# driver_led_v12.net
KiCad netlist of a schematic drawn in EAGLE
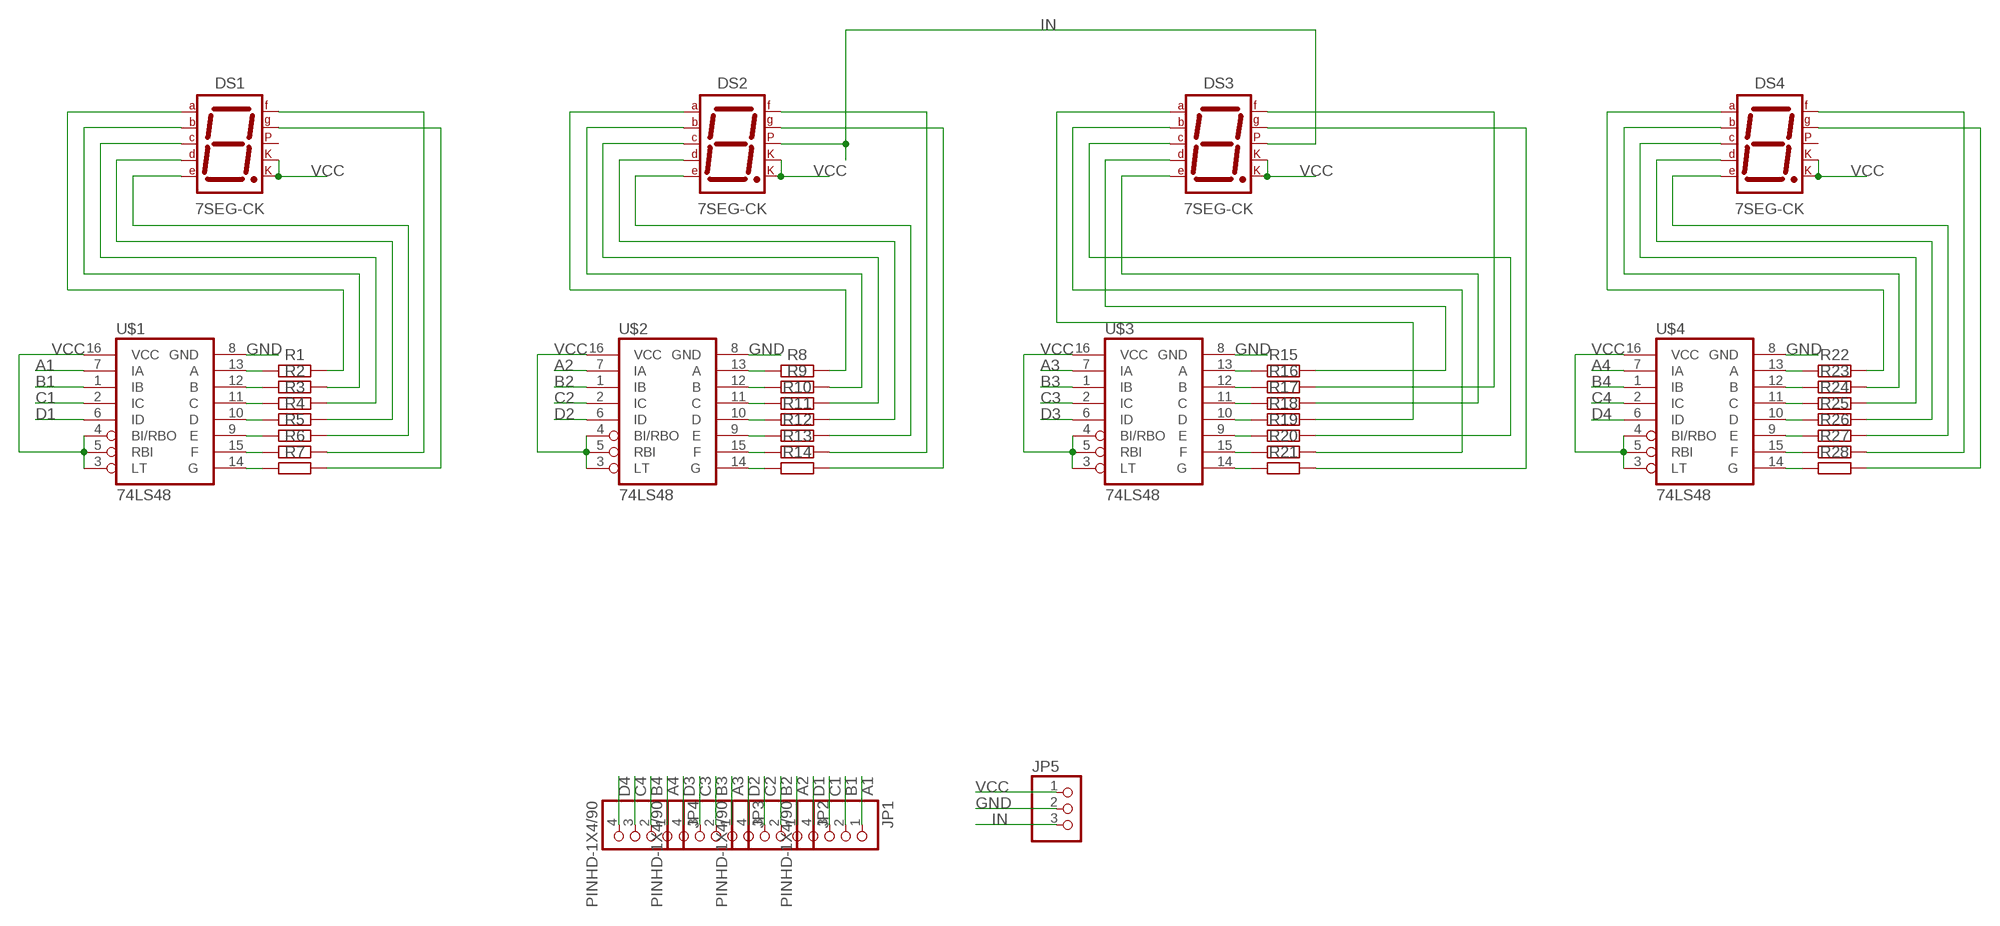
[diagram p0: schematic, sheet 1]

(export (version "E")
  (design (tool "Eeschema 10.0.6"))
  (components
    (comp (ref "DS1")
      (value "7SEG-CK")
      (footprint "eagle-import:7SEG-13")
      (libsource (lib "eagle-import") (part "7SEG-CK"))
    )
    (comp (ref "DS2")
      (value "7SEG-CK")
      (footprint "eagle-import:7SEG-13")
      (libsource (lib "eagle-import") (part "7SEG-CK"))
    )
    (comp (ref "DS3")
      (value "7SEG-CK")
      (footprint "eagle-import:7SEG-13")
      (libsource (lib "eagle-import") (part "7SEG-CK"))
    )
    (comp (ref "DS4")
      (value "7SEG-CK")
      (footprint "eagle-import:7SEG-13")
      (libsource (lib "eagle-import") (part "7SEG-CK"))
    )
    (comp (ref "JP1")
      (value "PINHD-1X4/90")
      (footprint "eagle-import:1X04_90")
      (libsource (lib "eagle-import") (part "PINHD-1X4/90"))
    )
    (comp (ref "JP2")
      (value "PINHD-1X4/90")
      (footprint "eagle-import:1X04_90")
      (libsource (lib "eagle-import") (part "PINHD-1X4/90"))
    )
    (comp (ref "JP3")
      (value "PINHD-1X4/90")
      (footprint "eagle-import:1X04_90")
      (libsource (lib "eagle-import") (part "PINHD-1X4/90"))
    )
    (comp (ref "JP4")
      (value "PINHD-1X4/90")
      (footprint "eagle-import:1X04_90")
      (libsource (lib "eagle-import") (part "PINHD-1X4/90"))
    )
    (comp (ref "JP5")
      (value "PINHD-1X3CB")
      (footprint "eagle-import:1X03-CLEANBIG")
      (libsource (lib "eagle-import") (part "PINHD-1X3CB"))
    )
    (comp (ref "R1")
      (value "R_AXIAL-7.2MM-PITCH")
      (footprint "eagle-import:RESAD724W46L381D178B")
      (libsource (lib "eagle-import") (part "RAXIAL-7.2MM-PITCH_"))
    )
    (comp (ref "R2")
      (value "R_AXIAL-7.2MM-PITCH")
      (footprint "eagle-import:RESAD724W46L381D178B")
      (libsource (lib "eagle-import") (part "RAXIAL-7.2MM-PITCH_"))
    )
    (comp (ref "R3")
      (value "R_AXIAL-7.2MM-PITCH")
      (footprint "eagle-import:RESAD724W46L381D178B")
      (libsource (lib "eagle-import") (part "RAXIAL-7.2MM-PITCH_"))
    )
    (comp (ref "R4")
      (value "R_AXIAL-7.2MM-PITCH")
      (footprint "eagle-import:RESAD724W46L381D178B")
      (libsource (lib "eagle-import") (part "RAXIAL-7.2MM-PITCH_"))
    )
    (comp (ref "R5")
      (value "R_AXIAL-7.2MM-PITCH")
      (footprint "eagle-import:RESAD724W46L381D178B")
      (libsource (lib "eagle-import") (part "RAXIAL-7.2MM-PITCH_"))
    )
    (comp (ref "R6")
      (value "R_AXIAL-7.2MM-PITCH")
      (footprint "eagle-import:RESAD724W46L381D178B")
      (libsource (lib "eagle-import") (part "RAXIAL-7.2MM-PITCH_"))
    )
    (comp (ref "R7")
      (value "R_AXIAL-7.2MM-PITCH")
      (footprint "eagle-import:RESAD724W46L381D178B")
      (libsource (lib "eagle-import") (part "RAXIAL-7.2MM-PITCH_"))
    )
    (comp (ref "R8")
      (value "R_AXIAL-7.2MM-PITCH")
      (footprint "eagle-import:RESAD724W46L381D178B")
      (libsource (lib "eagle-import") (part "RAXIAL-7.2MM-PITCH_"))
    )
    (comp (ref "R9")
      (value "R_AXIAL-7.2MM-PITCH")
      (footprint "eagle-import:RESAD724W46L381D178B")
      (libsource (lib "eagle-import") (part "RAXIAL-7.2MM-PITCH_"))
    )
    (comp (ref "R10")
      (value "R_AXIAL-7.2MM-PITCH")
      (footprint "eagle-import:RESAD724W46L381D178B")
      (libsource (lib "eagle-import") (part "RAXIAL-7.2MM-PITCH_"))
    )
    (comp (ref "R11")
      (value "R_AXIAL-7.2MM-PITCH")
      (footprint "eagle-import:RESAD724W46L381D178B")
      (libsource (lib "eagle-import") (part "RAXIAL-7.2MM-PITCH_"))
    )
    (comp (ref "R12")
      (value "R_AXIAL-7.2MM-PITCH")
      (footprint "eagle-import:RESAD724W46L381D178B")
      (libsource (lib "eagle-import") (part "RAXIAL-7.2MM-PITCH_"))
    )
    (comp (ref "R13")
      (value "R_AXIAL-7.2MM-PITCH")
      (footprint "eagle-import:RESAD724W46L381D178B")
      (libsource (lib "eagle-import") (part "RAXIAL-7.2MM-PITCH_"))
    )
    (comp (ref "R14")
      (value "R_AXIAL-7.2MM-PITCH")
      (footprint "eagle-import:RESAD724W46L381D178B")
      (libsource (lib "eagle-import") (part "RAXIAL-7.2MM-PITCH_"))
    )
    (comp (ref "R15")
      (value "R_AXIAL-7.2MM-PITCH")
      (footprint "eagle-import:RESAD724W46L381D178B")
      (libsource (lib "eagle-import") (part "RAXIAL-7.2MM-PITCH_"))
    )
    (comp (ref "R16")
      (value "R_AXIAL-7.2MM-PITCH")
      (footprint "eagle-import:RESAD724W46L381D178B")
      (libsource (lib "eagle-import") (part "RAXIAL-7.2MM-PITCH_"))
    )
    (comp (ref "R17")
      (value "R_AXIAL-7.2MM-PITCH")
      (footprint "eagle-import:RESAD724W46L381D178B")
      (libsource (lib "eagle-import") (part "RAXIAL-7.2MM-PITCH_"))
    )
    (comp (ref "R18")
      (value "R_AXIAL-7.2MM-PITCH")
      (footprint "eagle-import:RESAD724W46L381D178B")
      (libsource (lib "eagle-import") (part "RAXIAL-7.2MM-PITCH_"))
    )
    (comp (ref "R19")
      (value "R_AXIAL-7.2MM-PITCH")
      (footprint "eagle-import:RESAD724W46L381D178B")
      (libsource (lib "eagle-import") (part "RAXIAL-7.2MM-PITCH_"))
    )
    (comp (ref "R20")
      (value "R_AXIAL-7.2MM-PITCH")
      (footprint "eagle-import:RESAD724W46L381D178B")
      (libsource (lib "eagle-import") (part "RAXIAL-7.2MM-PITCH_"))
    )
    (comp (ref "R21")
      (value "R_AXIAL-7.2MM-PITCH")
      (footprint "eagle-import:RESAD724W46L381D178B")
      (libsource (lib "eagle-import") (part "RAXIAL-7.2MM-PITCH_"))
    )
    (comp (ref "R22")
      (value "R_AXIAL-7.2MM-PITCH")
      (footprint "eagle-import:RESAD724W46L381D178B")
      (libsource (lib "eagle-import") (part "RAXIAL-7.2MM-PITCH_"))
    )
    (comp (ref "R23")
      (value "R_AXIAL-7.2MM-PITCH")
      (footprint "eagle-import:RESAD724W46L381D178B")
      (libsource (lib "eagle-import") (part "RAXIAL-7.2MM-PITCH_"))
    )
    (comp (ref "R24")
      (value "R_AXIAL-7.2MM-PITCH")
      (footprint "eagle-import:RESAD724W46L381D178B")
      (libsource (lib "eagle-import") (part "RAXIAL-7.2MM-PITCH_"))
    )
    (comp (ref "R25")
      (value "R_AXIAL-7.2MM-PITCH")
      (footprint "eagle-import:RESAD724W46L381D178B")
      (libsource (lib "eagle-import") (part "RAXIAL-7.2MM-PITCH_"))
    )
    (comp (ref "R26")
      (value "R_AXIAL-7.2MM-PITCH")
      (footprint "eagle-import:RESAD724W46L381D178B")
      (libsource (lib "eagle-import") (part "RAXIAL-7.2MM-PITCH_"))
    )
    (comp (ref "R27")
      (value "R_AXIAL-7.2MM-PITCH")
      (footprint "eagle-import:RESAD724W46L381D178B")
      (libsource (lib "eagle-import") (part "RAXIAL-7.2MM-PITCH_"))
    )
    (comp (ref "R28")
      (value "R_AXIAL-7.2MM-PITCH")
      (footprint "eagle-import:RESAD724W46L381D178B")
      (libsource (lib "eagle-import") (part "RAXIAL-7.2MM-PITCH_"))
    )
    (comp (ref "U$1")
      (value "74LS48")
      (footprint "eagle-import:DIO16")
      (libsource (lib "eagle-import") (part "74LS48"))
    )
    (comp (ref "U$2")
      (value "74LS48")
      (footprint "eagle-import:DIO16")
      (libsource (lib "eagle-import") (part "74LS48"))
    )
    (comp (ref "U$3")
      (value "74LS48")
      (footprint "eagle-import:DIO16")
      (libsource (lib "eagle-import") (part "74LS48"))
    )
    (comp (ref "U$4")
      (value "74LS48")
      (footprint "eagle-import:DIO16")
      (libsource (lib "eagle-import") (part "74LS48"))
    )
  )
  (nets
    (net (code "1") (name "/A1") (class "Default")
      (node (ref "JP1") (pin "1") (pinfunction "1_1") (pintype "passive"))
      (node (ref "U$1") (pin "7") (pinfunction "IA_7") (pintype "input"))
    )
    (net (code "2") (name "/A2") (class "Default")
      (node (ref "JP2") (pin "1") (pinfunction "1_1") (pintype "passive"))
      (node (ref "U$2") (pin "7") (pinfunction "IA_7") (pintype "input"))
    )
    (net (code "3") (name "/A3") (class "Default")
      (node (ref "JP3") (pin "1") (pinfunction "1_1") (pintype "passive"))
      (node (ref "U$3") (pin "7") (pinfunction "IA_7") (pintype "input"))
    )
    (net (code "4") (name "/A4") (class "Default")
      (node (ref "JP4") (pin "1") (pinfunction "1_1") (pintype "passive"))
      (node (ref "U$4") (pin "7") (pinfunction "IA_7") (pintype "input"))
    )
    (net (code "5") (name "/B1") (class "Default")
      (node (ref "JP1") (pin "2") (pinfunction "2_2") (pintype "passive"))
      (node (ref "U$1") (pin "1") (pinfunction "IB_1") (pintype "input"))
    )
    (net (code "6") (name "/B2") (class "Default")
      (node (ref "JP2") (pin "2") (pinfunction "2_2") (pintype "passive"))
      (node (ref "U$2") (pin "1") (pinfunction "IB_1") (pintype "input"))
    )
    (net (code "7") (name "/B3") (class "Default")
      (node (ref "JP3") (pin "2") (pinfunction "2_2") (pintype "passive"))
      (node (ref "U$3") (pin "1") (pinfunction "IB_1") (pintype "input"))
    )
    (net (code "8") (name "/B4") (class "Default")
      (node (ref "JP4") (pin "2") (pinfunction "2_2") (pintype "passive"))
      (node (ref "U$4") (pin "1") (pinfunction "IB_1") (pintype "input"))
    )
    (net (code "9") (name "/C1") (class "Default")
      (node (ref "JP1") (pin "3") (pinfunction "3_3") (pintype "passive"))
      (node (ref "U$1") (pin "2") (pinfunction "IC_2") (pintype "input"))
    )
    (net (code "10") (name "/C2") (class "Default")
      (node (ref "JP2") (pin "3") (pinfunction "3_3") (pintype "passive"))
      (node (ref "U$2") (pin "2") (pinfunction "IC_2") (pintype "input"))
    )
    (net (code "11") (name "/C3") (class "Default")
      (node (ref "JP3") (pin "3") (pinfunction "3_3") (pintype "passive"))
      (node (ref "U$3") (pin "2") (pinfunction "IC_2") (pintype "input"))
    )
    (net (code "12") (name "/C4") (class "Default")
      (node (ref "JP4") (pin "3") (pinfunction "3_3") (pintype "passive"))
      (node (ref "U$4") (pin "2") (pinfunction "IC_2") (pintype "input"))
    )
    (net (code "13") (name "/D1") (class "Default")
      (node (ref "JP1") (pin "4") (pinfunction "4_4") (pintype "passive"))
      (node (ref "U$1") (pin "6") (pinfunction "ID_6") (pintype "input"))
    )
    (net (code "14") (name "/D2") (class "Default")
      (node (ref "JP2") (pin "4") (pinfunction "4_4") (pintype "passive"))
      (node (ref "U$2") (pin "6") (pinfunction "ID_6") (pintype "input"))
    )
    (net (code "15") (name "/D3") (class "Default")
      (node (ref "JP3") (pin "4") (pinfunction "4_4") (pintype "passive"))
      (node (ref "U$3") (pin "6") (pinfunction "ID_6") (pintype "input"))
    )
    (net (code "16") (name "/D4") (class "Default")
      (node (ref "JP4") (pin "4") (pinfunction "4_4") (pintype "passive"))
      (node (ref "U$4") (pin "6") (pinfunction "ID_6") (pintype "input"))
    )
    (net (code "17") (name "/GND") (class "Default")
      (node (ref "JP5") (pin "2") (pinfunction "2_2") (pintype "passive"))
      (node (ref "U$1") (pin "8") (pinfunction "GND_8") (pintype "bidirectional"))
      (node (ref "U$2") (pin "8") (pinfunction "GND_8") (pintype "bidirectional"))
      (node (ref "U$3") (pin "8") (pinfunction "GND_8") (pintype "bidirectional"))
      (node (ref "U$4") (pin "8") (pinfunction "GND_8") (pintype "bidirectional"))
    )
    (net (code "18") (name "/IN") (class "Default")
      (node (ref "DS2") (pin "5") (pinfunction "DP_5") (pintype "passive"))
      (node (ref "DS3") (pin "5") (pinfunction "DP_5") (pintype "passive"))
      (node (ref "JP5") (pin "3") (pinfunction "3_3") (pintype "passive"))
    )
    (net (code "19") (name "/VCC") (class "Default")
      (node (ref "DS1") (pin "3") (pinfunction "CK1_3") (pintype "passive"))
      (node (ref "DS1") (pin "8") (pinfunction "CK2_8") (pintype "passive"))
      (node (ref "DS2") (pin "3") (pinfunction "CK1_3") (pintype "passive"))
      (node (ref "DS2") (pin "8") (pinfunction "CK2_8") (pintype "passive"))
      (node (ref "DS3") (pin "3") (pinfunction "CK1_3") (pintype "passive"))
      (node (ref "DS3") (pin "8") (pinfunction "CK2_8") (pintype "passive"))
      (node (ref "DS4") (pin "3") (pinfunction "CK1_3") (pintype "passive"))
      (node (ref "DS4") (pin "8") (pinfunction "CK2_8") (pintype "passive"))
      (node (ref "JP5") (pin "1") (pinfunction "1_1") (pintype "passive"))
      (node (ref "U$1") (pin "16") (pinfunction "VCC_16") (pintype "bidirectional"))
      (node (ref "U$1") (pin "3") (pinfunction "LT_3") (pintype "input"))
      (node (ref "U$1") (pin "4") (pinfunction "BI/RBO_4") (pintype "input"))
      (node (ref "U$1") (pin "5") (pinfunction "RBI_5") (pintype "input"))
      (node (ref "U$2") (pin "16") (pinfunction "VCC_16") (pintype "bidirectional"))
      (node (ref "U$2") (pin "3") (pinfunction "LT_3") (pintype "input"))
      (node (ref "U$2") (pin "4") (pinfunction "BI/RBO_4") (pintype "input"))
      (node (ref "U$2") (pin "5") (pinfunction "RBI_5") (pintype "input"))
      (node (ref "U$3") (pin "16") (pinfunction "VCC_16") (pintype "bidirectional"))
      (node (ref "U$3") (pin "3") (pinfunction "LT_3") (pintype "input"))
      (node (ref "U$3") (pin "4") (pinfunction "BI/RBO_4") (pintype "input"))
      (node (ref "U$3") (pin "5") (pinfunction "RBI_5") (pintype "input"))
      (node (ref "U$4") (pin "16") (pinfunction "VCC_16") (pintype "bidirectional"))
      (node (ref "U$4") (pin "3") (pinfunction "LT_3") (pintype "input"))
      (node (ref "U$4") (pin "4") (pinfunction "BI/RBO_4") (pintype "input"))
      (node (ref "U$4") (pin "5") (pinfunction "RBI_5") (pintype "input"))
    )
    (net (code "20") (name "Net-(DS1-A)") (class "Default")
      (node (ref "DS1") (pin "7") (pinfunction "A_7") (pintype "passive"))
      (node (ref "R1") (pin "2") (pinfunction "2_2") (pintype "passive"))
    )
    (net (code "21") (name "Net-(DS1-B)") (class "Default")
      (node (ref "DS1") (pin "6") (pinfunction "B_6") (pintype "passive"))
      (node (ref "R2") (pin "2") (pinfunction "2_2") (pintype "passive"))
    )
    (net (code "22") (name "Net-(DS1-C)") (class "Default")
      (node (ref "DS1") (pin "4") (pinfunction "C_4") (pintype "passive"))
      (node (ref "R3") (pin "2") (pinfunction "2_2") (pintype "passive"))
    )
    (net (code "23") (name "Net-(DS1-D)") (class "Default")
      (node (ref "DS1") (pin "2") (pinfunction "D_2") (pintype "passive"))
      (node (ref "R4") (pin "2") (pinfunction "2_2") (pintype "passive"))
    )
    (net (code "24") (name "Net-(DS1-E)") (class "Default")
      (node (ref "DS1") (pin "1") (pinfunction "E_1") (pintype "passive"))
      (node (ref "R5") (pin "2") (pinfunction "2_2") (pintype "passive"))
    )
    (net (code "25") (name "Net-(DS1-F)") (class "Default")
      (node (ref "DS1") (pin "9") (pinfunction "F_9") (pintype "passive"))
      (node (ref "R6") (pin "2") (pinfunction "2_2") (pintype "passive"))
    )
    (net (code "26") (name "Net-(DS1-G)") (class "Default")
      (node (ref "DS1") (pin "10") (pinfunction "G_10") (pintype "passive"))
      (node (ref "R7") (pin "2") (pinfunction "2_2") (pintype "passive"))
    )
    (net (code "27") (name "Net-(DS2-A)") (class "Default")
      (node (ref "DS2") (pin "7") (pinfunction "A_7") (pintype "passive"))
      (node (ref "R8") (pin "2") (pinfunction "2_2") (pintype "passive"))
    )
    (net (code "28") (name "Net-(DS2-B)") (class "Default")
      (node (ref "DS2") (pin "6") (pinfunction "B_6") (pintype "passive"))
      (node (ref "R9") (pin "2") (pinfunction "2_2") (pintype "passive"))
    )
    (net (code "29") (name "Net-(DS2-C)") (class "Default")
      (node (ref "DS2") (pin "4") (pinfunction "C_4") (pintype "passive"))
      (node (ref "R10") (pin "2") (pinfunction "2_2") (pintype "passive"))
    )
    (net (code "30") (name "Net-(DS2-D)") (class "Default")
      (node (ref "DS2") (pin "2") (pinfunction "D_2") (pintype "passive"))
      (node (ref "R11") (pin "2") (pinfunction "2_2") (pintype "passive"))
    )
    (net (code "31") (name "Net-(DS2-E)") (class "Default")
      (node (ref "DS2") (pin "1") (pinfunction "E_1") (pintype "passive"))
      (node (ref "R12") (pin "2") (pinfunction "2_2") (pintype "passive"))
    )
    (net (code "32") (name "Net-(DS2-F)") (class "Default")
      (node (ref "DS2") (pin "9") (pinfunction "F_9") (pintype "passive"))
      (node (ref "R13") (pin "2") (pinfunction "2_2") (pintype "passive"))
    )
    (net (code "33") (name "Net-(DS2-G)") (class "Default")
      (node (ref "DS2") (pin "10") (pinfunction "G_10") (pintype "passive"))
      (node (ref "R14") (pin "2") (pinfunction "2_2") (pintype "passive"))
    )
    (net (code "34") (name "Net-(DS3-A)") (class "Default")
      (node (ref "DS3") (pin "7") (pinfunction "A_7") (pintype "passive"))
      (node (ref "R18") (pin "2") (pinfunction "2_2") (pintype "passive"))
    )
    (net (code "35") (name "Net-(DS3-B)") (class "Default")
      (node (ref "DS3") (pin "6") (pinfunction "B_6") (pintype "passive"))
      (node (ref "R20") (pin "2") (pinfunction "2_2") (pintype "passive"))
    )
    (net (code "36") (name "Net-(DS3-C)") (class "Default")
      (node (ref "DS3") (pin "4") (pinfunction "C_4") (pintype "passive"))
      (node (ref "R19") (pin "2") (pinfunction "2_2") (pintype "passive"))
    )
    (net (code "37") (name "Net-(DS3-D)") (class "Default")
      (node (ref "DS3") (pin "2") (pinfunction "D_2") (pintype "passive"))
      (node (ref "R15") (pin "2") (pinfunction "2_2") (pintype "passive"))
    )
    (net (code "38") (name "Net-(DS3-E)") (class "Default")
      (node (ref "DS3") (pin "1") (pinfunction "E_1") (pintype "passive"))
      (node (ref "R17") (pin "2") (pinfunction "2_2") (pintype "passive"))
    )
    (net (code "39") (name "Net-(DS3-F)") (class "Default")
      (node (ref "DS3") (pin "9") (pinfunction "F_9") (pintype "passive"))
      (node (ref "R16") (pin "2") (pinfunction "2_2") (pintype "passive"))
    )
    (net (code "40") (name "Net-(DS3-G)") (class "Default")
      (node (ref "DS3") (pin "10") (pinfunction "G_10") (pintype "passive"))
      (node (ref "R21") (pin "2") (pinfunction "2_2") (pintype "passive"))
    )
    (net (code "41") (name "Net-(DS4-A)") (class "Default")
      (node (ref "DS4") (pin "7") (pinfunction "A_7") (pintype "passive"))
      (node (ref "R22") (pin "2") (pinfunction "2_2") (pintype "passive"))
    )
    (net (code "42") (name "Net-(DS4-B)") (class "Default")
      (node (ref "DS4") (pin "6") (pinfunction "B_6") (pintype "passive"))
      (node (ref "R23") (pin "2") (pinfunction "2_2") (pintype "passive"))
    )
    (net (code "43") (name "Net-(DS4-C)") (class "Default")
      (node (ref "DS4") (pin "4") (pinfunction "C_4") (pintype "passive"))
      (node (ref "R24") (pin "2") (pinfunction "2_2") (pintype "passive"))
    )
    (net (code "44") (name "Net-(DS4-D)") (class "Default")
      (node (ref "DS4") (pin "2") (pinfunction "D_2") (pintype "passive"))
      (node (ref "R25") (pin "2") (pinfunction "2_2") (pintype "passive"))
    )
    (net (code "45") (name "Net-(DS4-E)") (class "Default")
      (node (ref "DS4") (pin "1") (pinfunction "E_1") (pintype "passive"))
      (node (ref "R26") (pin "2") (pinfunction "2_2") (pintype "passive"))
    )
    (net (code "46") (name "Net-(DS4-F)") (class "Default")
      (node (ref "DS4") (pin "9") (pinfunction "F_9") (pintype "passive"))
      (node (ref "R27") (pin "2") (pinfunction "2_2") (pintype "passive"))
    )
    (net (code "47") (name "Net-(DS4-G)") (class "Default")
      (node (ref "DS4") (pin "10") (pinfunction "G_10") (pintype "passive"))
      (node (ref "R28") (pin "2") (pinfunction "2_2") (pintype "passive"))
    )
    (net (code "48") (name "Net-(U$1-A)") (class "Default")
      (node (ref "R1") (pin "1") (pinfunction "1_1") (pintype "passive"))
      (node (ref "U$1") (pin "13") (pinfunction "A_13") (pintype "output"))
    )
    (net (code "49") (name "Net-(U$1-B)") (class "Default")
      (node (ref "R2") (pin "1") (pinfunction "1_1") (pintype "passive"))
      (node (ref "U$1") (pin "12") (pinfunction "B_12") (pintype "output"))
    )
    (net (code "50") (name "Net-(U$1-C)") (class "Default")
      (node (ref "R3") (pin "1") (pinfunction "1_1") (pintype "passive"))
      (node (ref "U$1") (pin "11") (pinfunction "C_11") (pintype "output"))
    )
    (net (code "51") (name "Net-(U$1-D)") (class "Default")
      (node (ref "R4") (pin "1") (pinfunction "1_1") (pintype "passive"))
      (node (ref "U$1") (pin "10") (pinfunction "D_10") (pintype "output"))
    )
    (net (code "52") (name "Net-(U$1-E)") (class "Default")
      (node (ref "R5") (pin "1") (pinfunction "1_1") (pintype "passive"))
      (node (ref "U$1") (pin "9") (pinfunction "E_9") (pintype "output"))
    )
    (net (code "53") (name "Net-(U$1-F)") (class "Default")
      (node (ref "R6") (pin "1") (pinfunction "1_1") (pintype "passive"))
      (node (ref "U$1") (pin "15") (pinfunction "F_15") (pintype "output"))
    )
    (net (code "54") (name "Net-(U$1-G)") (class "Default")
      (node (ref "R7") (pin "1") (pinfunction "1_1") (pintype "passive"))
      (node (ref "U$1") (pin "14") (pinfunction "G_14") (pintype "output"))
    )
    (net (code "55") (name "Net-(U$2-A)") (class "Default")
      (node (ref "R8") (pin "1") (pinfunction "1_1") (pintype "passive"))
      (node (ref "U$2") (pin "13") (pinfunction "A_13") (pintype "output"))
    )
    (net (code "56") (name "Net-(U$2-B)") (class "Default")
      (node (ref "R9") (pin "1") (pinfunction "1_1") (pintype "passive"))
      (node (ref "U$2") (pin "12") (pinfunction "B_12") (pintype "output"))
    )
    (net (code "57") (name "Net-(U$2-C)") (class "Default")
      (node (ref "R10") (pin "1") (pinfunction "1_1") (pintype "passive"))
      (node (ref "U$2") (pin "11") (pinfunction "C_11") (pintype "output"))
    )
    (net (code "58") (name "Net-(U$2-D)") (class "Default")
      (node (ref "R11") (pin "1") (pinfunction "1_1") (pintype "passive"))
      (node (ref "U$2") (pin "10") (pinfunction "D_10") (pintype "output"))
    )
    (net (code "59") (name "Net-(U$2-E)") (class "Default")
      (node (ref "R12") (pin "1") (pinfunction "1_1") (pintype "passive"))
      (node (ref "U$2") (pin "9") (pinfunction "E_9") (pintype "output"))
    )
    (net (code "60") (name "Net-(U$2-F)") (class "Default")
      (node (ref "R13") (pin "1") (pinfunction "1_1") (pintype "passive"))
      (node (ref "U$2") (pin "15") (pinfunction "F_15") (pintype "output"))
    )
    (net (code "61") (name "Net-(U$2-G)") (class "Default")
      (node (ref "R14") (pin "1") (pinfunction "1_1") (pintype "passive"))
      (node (ref "U$2") (pin "14") (pinfunction "G_14") (pintype "output"))
    )
    (net (code "62") (name "Net-(U$3-A)") (class "Default")
      (node (ref "R15") (pin "1") (pinfunction "1_1") (pintype "passive"))
      (node (ref "U$3") (pin "13") (pinfunction "A_13") (pintype "output"))
    )
    (net (code "63") (name "Net-(U$3-B)") (class "Default")
      (node (ref "R16") (pin "1") (pinfunction "1_1") (pintype "passive"))
      (node (ref "U$3") (pin "12") (pinfunction "B_12") (pintype "output"))
    )
    (net (code "64") (name "Net-(U$3-C)") (class "Default")
      (node (ref "R17") (pin "1") (pinfunction "1_1") (pintype "passive"))
      (node (ref "U$3") (pin "11") (pinfunction "C_11") (pintype "output"))
    )
    (net (code "65") (name "Net-(U$3-D)") (class "Default")
      (node (ref "R18") (pin "1") (pinfunction "1_1") (pintype "passive"))
      (node (ref "U$3") (pin "10") (pinfunction "D_10") (pintype "output"))
    )
    (net (code "66") (name "Net-(U$3-E)") (class "Default")
      (node (ref "R19") (pin "1") (pinfunction "1_1") (pintype "passive"))
      (node (ref "U$3") (pin "9") (pinfunction "E_9") (pintype "output"))
    )
    (net (code "67") (name "Net-(U$3-F)") (class "Default")
      (node (ref "R20") (pin "1") (pinfunction "1_1") (pintype "passive"))
      (node (ref "U$3") (pin "15") (pinfunction "F_15") (pintype "output"))
    )
    (net (code "68") (name "Net-(U$3-G)") (class "Default")
      (node (ref "R21") (pin "1") (pinfunction "1_1") (pintype "passive"))
      (node (ref "U$3") (pin "14") (pinfunction "G_14") (pintype "output"))
    )
    (net (code "69") (name "Net-(U$4-A)") (class "Default")
      (node (ref "R22") (pin "1") (pinfunction "1_1") (pintype "passive"))
      (node (ref "U$4") (pin "13") (pinfunction "A_13") (pintype "output"))
    )
    (net (code "70") (name "Net-(U$4-B)") (class "Default")
      (node (ref "R23") (pin "1") (pinfunction "1_1") (pintype "passive"))
      (node (ref "U$4") (pin "12") (pinfunction "B_12") (pintype "output"))
    )
    (net (code "71") (name "Net-(U$4-C)") (class "Default")
      (node (ref "R24") (pin "1") (pinfunction "1_1") (pintype "passive"))
      (node (ref "U$4") (pin "11") (pinfunction "C_11") (pintype "output"))
    )
    (net (code "72") (name "Net-(U$4-D)") (class "Default")
      (node (ref "R25") (pin "1") (pinfunction "1_1") (pintype "passive"))
      (node (ref "U$4") (pin "10") (pinfunction "D_10") (pintype "output"))
    )
    (net (code "73") (name "Net-(U$4-E)") (class "Default")
      (node (ref "R26") (pin "1") (pinfunction "1_1") (pintype "passive"))
      (node (ref "U$4") (pin "9") (pinfunction "E_9") (pintype "output"))
    )
    (net (code "74") (name "Net-(U$4-F)") (class "Default")
      (node (ref "R27") (pin "1") (pinfunction "1_1") (pintype "passive"))
      (node (ref "U$4") (pin "15") (pinfunction "F_15") (pintype "output"))
    )
    (net (code "75") (name "Net-(U$4-G)") (class "Default")
      (node (ref "R28") (pin "1") (pinfunction "1_1") (pintype "passive"))
      (node (ref "U$4") (pin "14") (pinfunction "G_14") (pintype "output"))
    )
    (net (code "76") (name "unconnected-(DS1-DP-Pad5)") (class "Default")
      (node (ref "DS1") (pin "5") (pinfunction "DP_5") (pintype "passive"))
    )
    (net (code "77") (name "unconnected-(DS4-DP-Pad5)") (class "Default")
      (node (ref "DS4") (pin "5") (pinfunction "DP_5") (pintype "passive"))
    )
  )
)
